# untitled.net
KiCad netlist of a schematic drawn in EAGLE
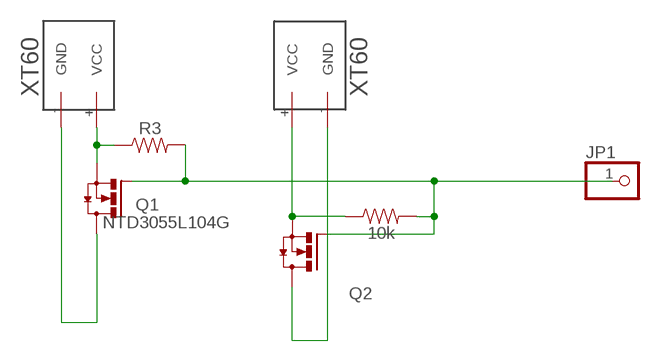
[diagram p0: schematic, sheet 1]

(export (version "E")
  (design (tool "Eeschema 10.0.6"))
  (components
    (comp (ref "JP1")
      (value "PINHD-1X1")
      (footprint "eagle-import:1X01")
      (libsource (lib "eagle-import") (part "PINHD-1X1"))
    )
    (comp (ref "Q1")
      (value "NTD3055L104G")
      (footprint "eagle-import:DPAK4")
      (fields (field (name "MANUFACTURER") "ON SEMICONDUCTORS") (field (name "CREATED_BY") "PCBLayout.com"))
      (libsource (lib "eagle-import") (part "NTD3055L104G"))
    )
    (comp (ref "Q2")
      (value "NTD3055L104G")
      (footprint "eagle-import:DPAK4")
      (fields (field (name "MANUFACTURER") "ON SEMICONDUCTORS") (field (name "CREATED_BY") "PCBLayout.com"))
      (libsource (lib "eagle-import") (part "NTD3055L104G"))
    )
    (comp (ref "R3")
      (value "10k")
      (footprint "eagle-import:0402")
      (libsource (lib "eagle-import") (part "10KOHM-0402-1/16W-1%"))
    )
    (comp (ref "R4")
      (value "10k")
      (footprint "eagle-import:0402")
      (libsource (lib "eagle-import") (part "10KOHM-0402-1/16W-1%"))
    )
    (comp (ref "U$1")
      (value "XT60")
      (footprint "eagle-import:XT60")
      (libsource (lib "eagle-import") (part "XT60"))
    )
    (comp (ref "U$2")
      (value "XT60")
      (footprint "eagle-import:XT60")
      (libsource (lib "eagle-import") (part "XT60"))
    )
  )
  (nets
    (net (code "1") (name "Net-(Q1-G)") (class "Default")
      (node (ref "JP1") (pin "1") (pinfunction "1_1") (pintype "passive"))
      (node (ref "Q1") (pin "1") (pinfunction "G_1") (pintype "passive"))
      (node (ref "Q2") (pin "1") (pinfunction "G_1") (pintype "passive"))
      (node (ref "R3") (pin "2") (pinfunction "2_2") (pintype "passive"))
      (node (ref "R4") (pin "2") (pinfunction "2_2") (pintype "passive"))
    )
    (net (code "2") (name "Net-(Q1-S)") (class "Default")
      (node (ref "Q1") (pin "3") (pinfunction "S_3") (pintype "passive"))
      (node (ref "R3") (pin "1") (pinfunction "1_1") (pintype "passive"))
      (node (ref "U$1") (pin "+") (pinfunction "VCC_+") (pintype "bidirectional"))
    )
    (net (code "3") (name "Net-(Q2-S)") (class "Default")
      (node (ref "Q2") (pin "3") (pinfunction "S_3") (pintype "passive"))
      (node (ref "R4") (pin "1") (pinfunction "1_1") (pintype "passive"))
      (node (ref "U$2") (pin "+") (pinfunction "VCC_+") (pintype "bidirectional"))
    )
    (net (code "4") (name "Net-(U$1-GND)") (class "Default")
      (node (ref "Q1") (pin "2") (pinfunction "D_2") (pintype "passive"))
      (node (ref "Q1") (pin "4") (pinfunction "D_4") (pintype "passive"))
      (node (ref "U$1") (pin "-") (pinfunction "GND_-") (pintype "bidirectional"))
    )
    (net (code "5") (name "Net-(U$2-GND)") (class "Default")
      (node (ref "Q2") (pin "2") (pinfunction "D_2") (pintype "passive"))
      (node (ref "Q2") (pin "4") (pinfunction "D_4") (pintype "passive"))
      (node (ref "U$2") (pin "-") (pinfunction "GND_-") (pintype "bidirectional"))
    )
  )
)
